# 24Vto12V.net
KiCad netlist of a schematic drawn in Altium Designer
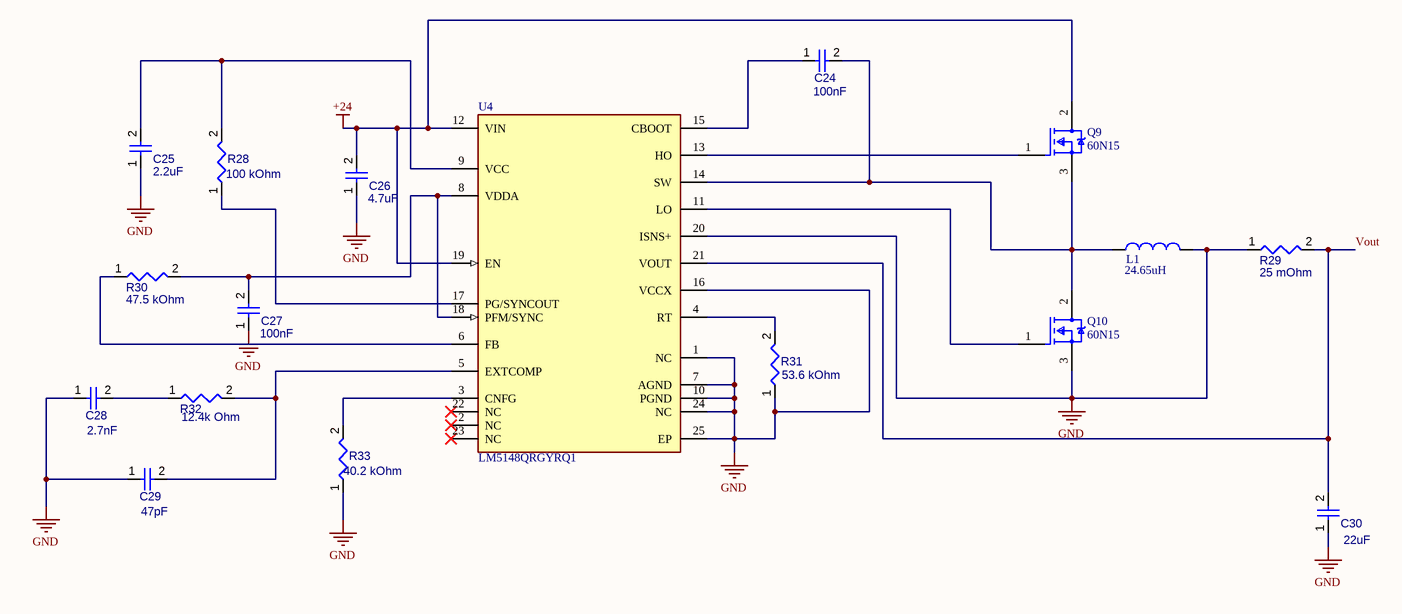
[diagram p0: 24Vto12V.SchDoc]

(export (version "E")
  (design (tool "Eeschema 10.0.6"))
  (components
    (comp (ref "C24") (value "100nF") (libsource (lib "Rahulb 23") (part "CAP-NP-2")))
    (comp (ref "C25") (value "2.2uF") (libsource (lib "Rahulb 23") (part "CAP-NP-2")))
    (comp (ref "C26") (value "4.7uF") (libsource (lib "Rahulb 23") (part "CAP-NP-2")))
    (comp (ref "C27") (value "100nF") (libsource (lib "Rahulb 23") (part "CAP-NP-2")))
    (comp (ref "C28") (value "2.7nF") (libsource (lib "Rahulb 23") (part "CAP-NP-2")))
    (comp (ref "C29") (value "47pF") (libsource (lib "Rahulb 23") (part "CAP-NP-2")))
    (comp (ref "C30") (value "22uF") (libsource (lib "Rahulb 23") (part "CAP-NP-2")))
    (comp (ref "L1") (value "24.65uH") (libsource (lib "Rahulb 23") (part "IND-2")))
    (comp (ref "Q9")
      (value "60N15")
      (footprint "FP-TO-220AB-MFG")
      (description "60N15 150V 60A N-Channel MOSFET TO-220")
      (libsource (lib "Altium Content Vault") (part "8b62d417cbef8344eebe0bde0c45977"))
    )
    (comp (ref "Q10")
      (value "60N15")
      (footprint "FP-TO-220AB-MFG")
      (description "60N15 150V 60A N-Channel MOSFET TO-220")
      (libsource (lib "Altium Content Vault") (part "8b62d417cbef8344eebe0bde0c45977"))
    )
    (comp (ref "R28") (value "100 kOhm") (libsource (lib "Rahulb 23") (part "RES-2")))
    (comp (ref "R29") (value "25 mOhm") (libsource (lib "Rahulb 23") (part "RES-2")))
    (comp (ref "R30") (value "47.5 kOhm") (libsource (lib "Rahulb 23") (part "RES-2")))
    (comp (ref "R31") (value "53.6 kOhm") (libsource (lib "Rahulb 23") (part "RES-2")))
    (comp (ref "R32") (value "12.4k Ohm") (libsource (lib "Rahulb 23") (part "RES-2")))
    (comp (ref "R33") (value "40.2 kOhm") (libsource (lib "Rahulb 23") (part "RES-2")))
    (comp (ref "U4")
      (value "LM5148QRGYRQ1")
      (footprint "FP-RGY0024E-MFG")
      (libsource (lib "Altium Content Vault") (part "ab60acdb83b3e8c6cb53feaa4ccc0a4"))
    )
  )
  (nets
    (net (code "1") (name "+24") (class "Default")
      (node (ref "C26") (pin "2") (pinfunction "2_2") (pintype "passive"))
      (node (ref "Q9") (pin "2") (pinfunction "DRAIN_2") (pintype "passive"))
      (node (ref "U4") (pin "12") (pinfunction "VIN_12") (pintype "power_in"))
      (node (ref "U4") (pin "19") (pinfunction "EN_19") (pintype "input"))
    )
    (net (code "2") (name "/Vout") (class "Default")
      (node (ref "C30") (pin "2") (pinfunction "2_2") (pintype "passive"))
      (node (ref "R29") (pin "2") (pinfunction "2_2") (pintype "passive"))
      (node (ref "U4") (pin "21") (pinfunction "VOUT_21") (pintype "passive"))
    )
    (net (code "3") (name "GND") (class "Default")
      (node (ref "C25") (pin "1") (pinfunction "1_1") (pintype "passive"))
      (node (ref "C26") (pin "1") (pinfunction "1_1") (pintype "passive"))
      (node (ref "C27") (pin "1") (pinfunction "1_1") (pintype "passive"))
      (node (ref "C28") (pin "1") (pinfunction "1_1") (pintype "passive"))
      (node (ref "C29") (pin "1") (pinfunction "1_1") (pintype "passive"))
      (node (ref "C30") (pin "1") (pinfunction "1_1") (pintype "passive"))
      (node (ref "L1") (pin "2") (pinfunction "2_2") (pintype "passive"))
      (node (ref "Q10") (pin "3") (pinfunction "SOURCE_3") (pintype "passive"))
      (node (ref "R29") (pin "1") (pinfunction "1_1") (pintype "passive"))
      (node (ref "R31") (pin "1") (pinfunction "1_1") (pintype "passive"))
      (node (ref "R33") (pin "1") (pinfunction "1_1") (pintype "passive"))
      (node (ref "U4") (pin "1") (pinfunction "NC_1") (pintype "passive"))
      (node (ref "U4") (pin "10") (pinfunction "PGND_10") (pintype "power_in"))
      (node (ref "U4") (pin "16") (pinfunction "VCCX_16") (pintype "power_in"))
      (node (ref "U4") (pin "20") (pinfunction "ISNS+_20") (pintype "passive"))
      (node (ref "U4") (pin "24") (pinfunction "NC_24") (pintype "passive"))
      (node (ref "U4") (pin "25") (pinfunction "EP_25") (pintype "passive"))
      (node (ref "U4") (pin "7") (pinfunction "AGND_7") (pintype "power_in"))
    )
    (net (code "4") (name "Net-(C28-Pad2)") (class "Default")
      (node (ref "C28") (pin "2") (pinfunction "2_2") (pintype "passive"))
      (node (ref "R32") (pin "1") (pinfunction "1_1") (pintype "passive"))
    )
    (net (code "5") (name "Net-(Q9-GATE)") (class "Default")
      (node (ref "Q9") (pin "1") (pinfunction "GATE_1") (pintype "passive"))
      (node (ref "U4") (pin "13") (pinfunction "HO_13") (pintype "passive"))
    )
    (net (code "6") (name "Net-(Q10-DRAIN)") (class "Default")
      (node (ref "C24") (pin "2") (pinfunction "2_2") (pintype "passive"))
      (node (ref "L1") (pin "1") (pinfunction "1_1") (pintype "passive"))
      (node (ref "Q10") (pin "2") (pinfunction "DRAIN_2") (pintype "passive"))
      (node (ref "Q9") (pin "3") (pinfunction "SOURCE_3") (pintype "passive"))
      (node (ref "U4") (pin "14") (pinfunction "SW_14") (pintype "power_in"))
    )
    (net (code "7") (name "Net-(Q10-GATE)") (class "Default")
      (node (ref "Q10") (pin "1") (pinfunction "GATE_1") (pintype "passive"))
      (node (ref "U4") (pin "11") (pinfunction "LO_11") (pintype "passive"))
    )
    (net (code "8") (name "Net-(U4-CBOOT)") (class "Default")
      (node (ref "C24") (pin "1") (pinfunction "1_1") (pintype "passive"))
      (node (ref "U4") (pin "15") (pinfunction "CBOOT_15") (pintype "power_in"))
    )
    (net (code "9") (name "Net-(U4-CNFG)") (class "Default")
      (node (ref "R33") (pin "2") (pinfunction "2_2") (pintype "passive"))
      (node (ref "U4") (pin "3") (pinfunction "CNFG_3") (pintype "passive"))
    )
    (net (code "10") (name "Net-(U4-EXTCOMP)") (class "Default")
      (node (ref "C29") (pin "2") (pinfunction "2_2") (pintype "passive"))
      (node (ref "R32") (pin "2") (pinfunction "2_2") (pintype "passive"))
      (node (ref "U4") (pin "5") (pinfunction "EXTCOMP_5") (pintype "passive"))
    )
    (net (code "11") (name "Net-(U4-FB)") (class "Default")
      (node (ref "R30") (pin "1") (pinfunction "1_1") (pintype "passive"))
      (node (ref "U4") (pin "6") (pinfunction "FB_6") (pintype "passive"))
    )
    (net (code "12") (name "Net-(U4-PFM{slash}SYNC)") (class "Default")
      (node (ref "C27") (pin "2") (pinfunction "2_2") (pintype "passive"))
      (node (ref "R30") (pin "2") (pinfunction "2_2") (pintype "passive"))
      (node (ref "U4") (pin "18") (pinfunction "PFM/SYNC_18") (pintype "input"))
      (node (ref "U4") (pin "8") (pinfunction "VDDA_8") (pintype "passive"))
    )
    (net (code "13") (name "Net-(U4-PG{slash}SYNCOUT)") (class "Default")
      (node (ref "R28") (pin "1") (pinfunction "1_1") (pintype "passive"))
      (node (ref "U4") (pin "17") (pinfunction "PG/SYNCOUT_17") (pintype "open_collector"))
    )
    (net (code "14") (name "Net-(U4-RT)") (class "Default")
      (node (ref "R31") (pin "2") (pinfunction "2_2") (pintype "passive"))
      (node (ref "U4") (pin "4") (pinfunction "RT_4") (pintype "passive"))
    )
    (net (code "15") (name "Net-(U4-VCC)") (class "Default")
      (node (ref "C25") (pin "2") (pinfunction "2_2") (pintype "passive"))
      (node (ref "R28") (pin "2") (pinfunction "2_2") (pintype "passive"))
      (node (ref "U4") (pin "9") (pinfunction "VCC_9") (pintype "power_in"))
    )
    (net (code "16") (name "unconnected-(U4-NC-Pad2)") (class "Default")
      (node (ref "U4") (pin "2") (pinfunction "NC_2") (pintype "passive+no_connect"))
    )
    (net (code "17") (name "unconnected-(U4-NC-Pad22)") (class "Default")
      (node (ref "U4") (pin "22") (pinfunction "NC_22") (pintype "passive+no_connect"))
    )
    (net (code "18") (name "unconnected-(U4-NC-Pad23)") (class "Default")
      (node (ref "U4") (pin "23") (pinfunction "NC_23") (pintype "passive+no_connect"))
    )
  )
)
